# Regulators1.net
KiCad netlist of a schematic drawn in Altium Designer
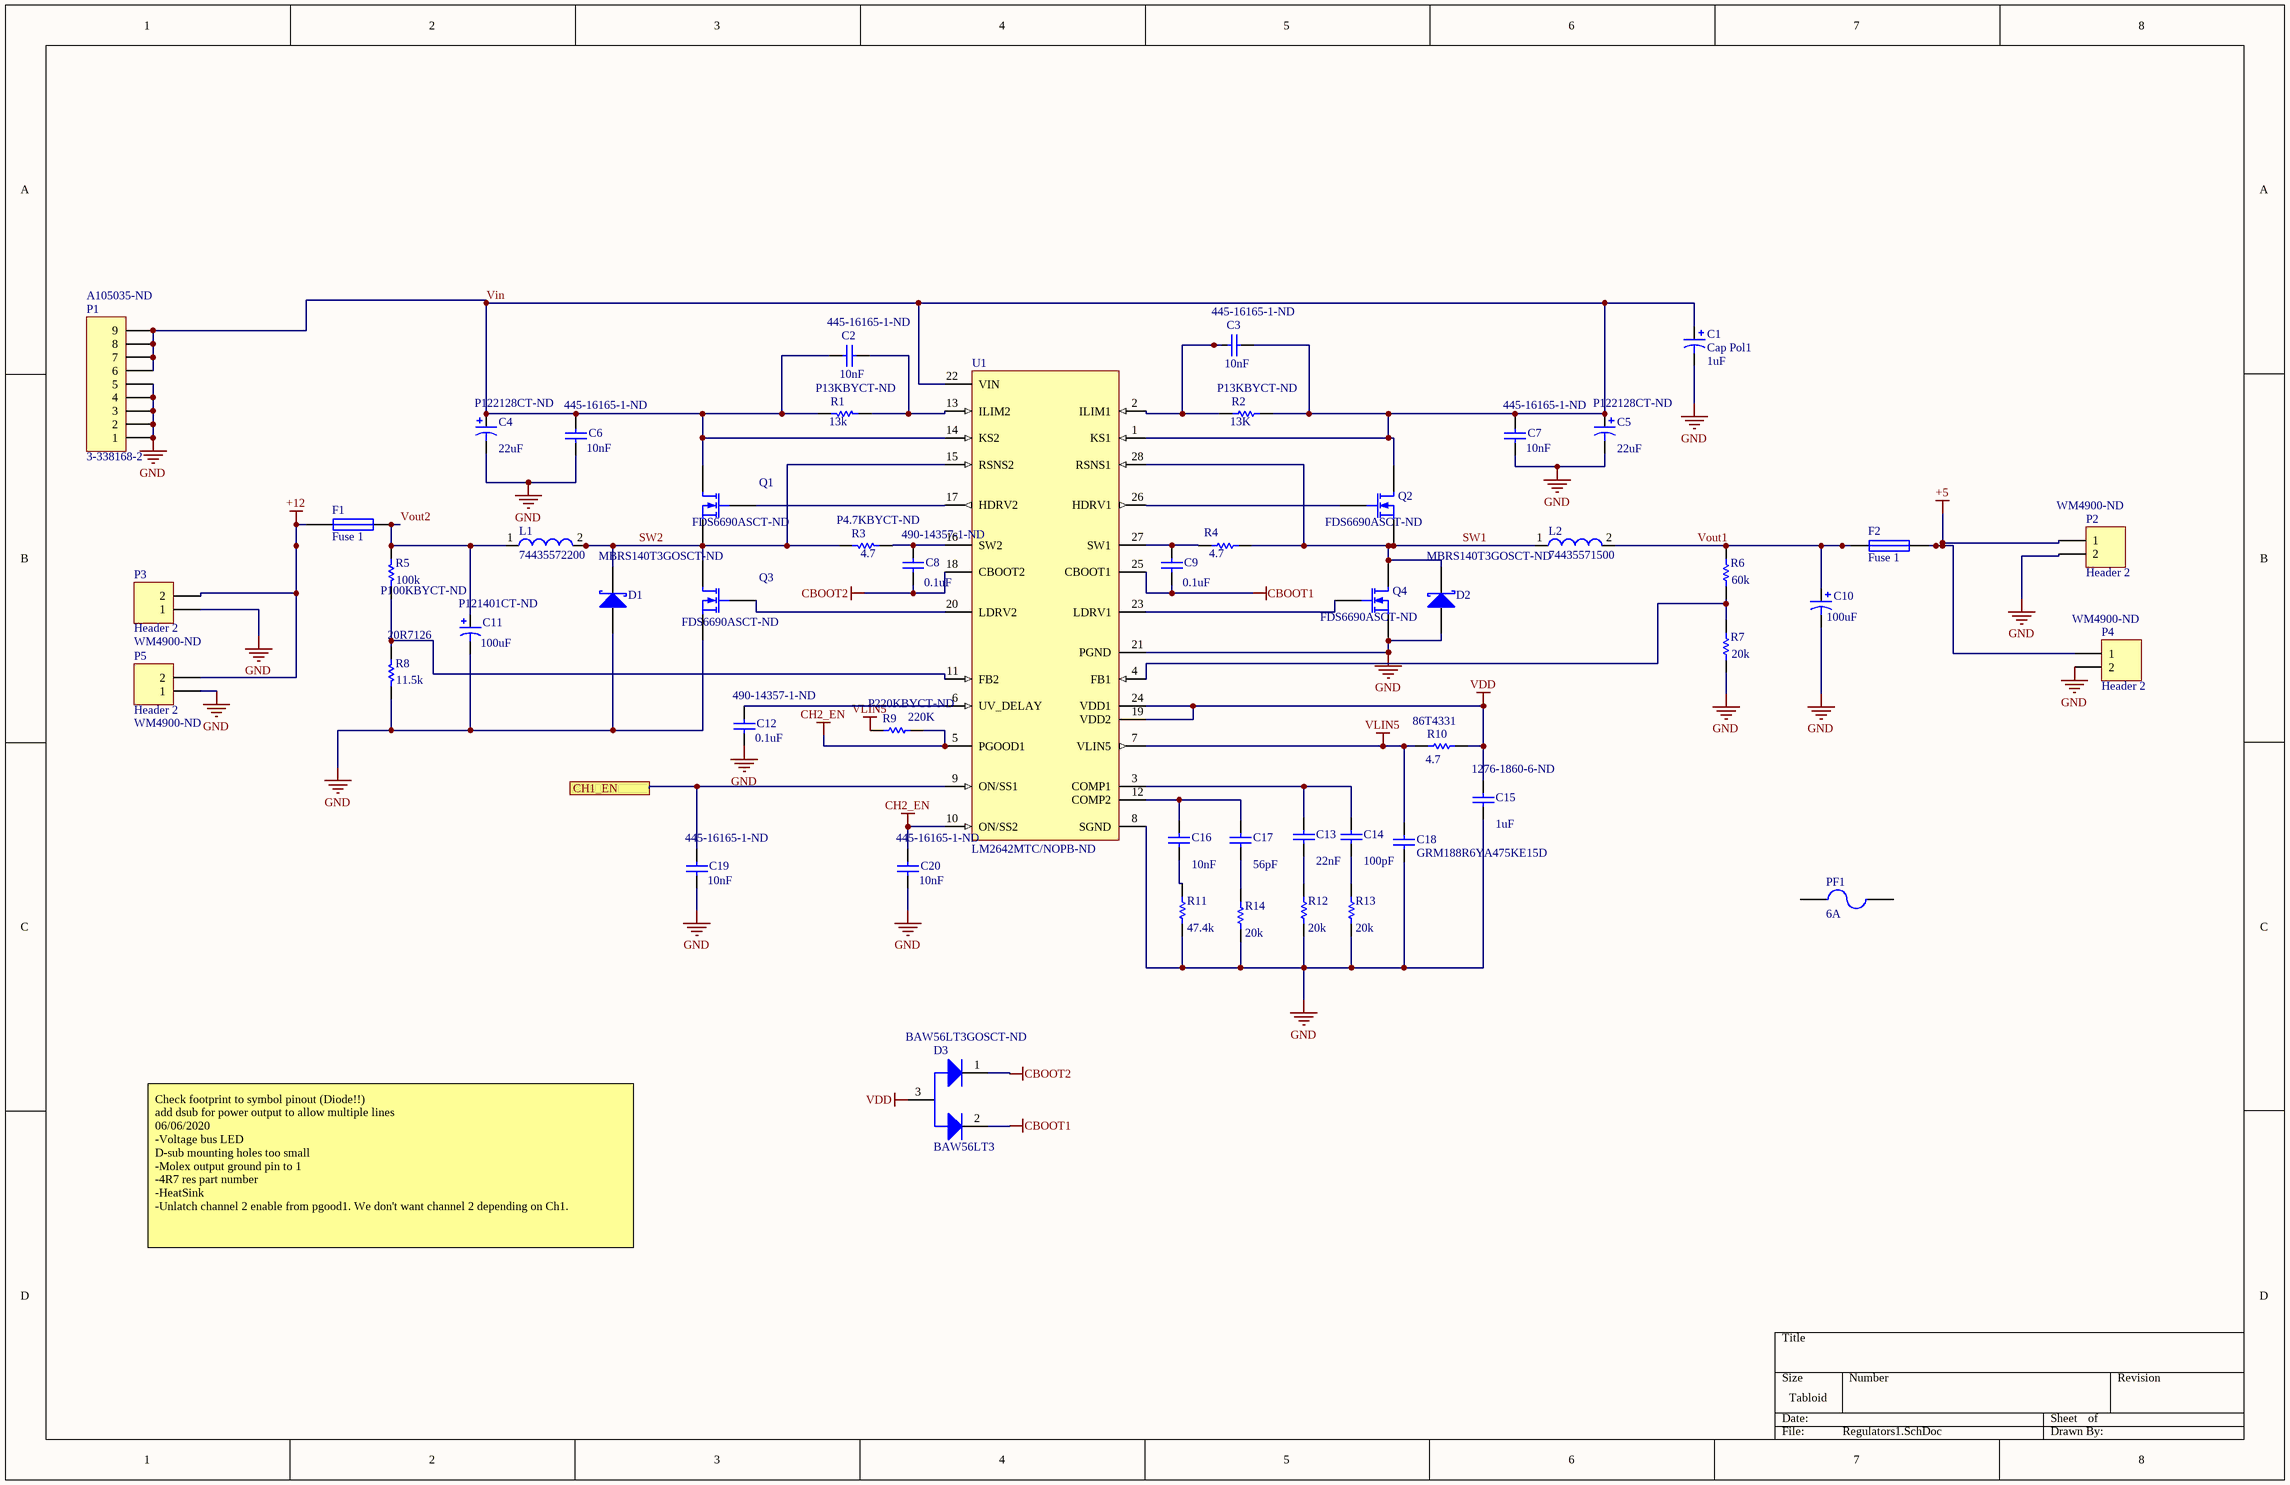
[diagram p0: Regulators1.SchDoc]

(export (version "E")
  (design (tool "Eeschema 10.0.6"))
  (components
    (comp (ref "C1")
      (value "Cap Pol1")
      (footprint "1u50VcapE")
      (description "Polarized Capacitor (Radial)")
      (fields (field (name "ALTIUM_VALUE") "1uF") (field (name "PUBLISHER") "Altium Limited"))
      (libsource (lib "") (part "Cap Pol1_1"))
    )
    (comp (ref "C2")
      (value "10nF")
      (footprint "1608[0603]")
      (description "CAP CER 10000PF 100V NP0 0603")
      (fields
        (field (name "SUPPLIER PART NUMBER 1") "445-16165-1-ND")
        (field (name "MANUFACTURER") "TDK")
        (field (name "MANUFACTURER PART NUMBER") "CGA3EANP02A103J080AC")
        (field (name "PUBLISHER") "Altium Limited")
      )
      (libsource (lib "Miscellaneous Devices") (part "Cap"))
    )
    (comp (ref "C3")
      (value "10nF")
      (footprint "1608[0603]")
      (description "CAP CER 10000PF 100V NP0 0603")
      (fields
        (field (name "SUPPLIER PART NUMBER 1") "445-16165-1-ND")
        (field (name "MANUFACTURER") "TDK")
        (field (name "MANUFACTURER PART NUMBER") "CGA3EANP02A103J080AC")
        (field (name "PUBLISHER") "Altium Limited")
      )
      (libsource (lib "Miscellaneous Devices") (part "Cap"))
    )
    (comp (ref "C4")
      (value "22uF")
      (footprint "CAPAE660X800N")
      (description "Polarized Capacitor (Radial)")
      (fields
        (field (name "SUPPLIER PART NUMBER 1") "P122128CT-ND")
        (field (name "Comment") "Cap Pol1")
        (field (name "PUBLISHER") "Altium Limited")
      )
      (libsource (lib "Miscellaneous Devices") (part "Cap Pol1"))
    )
    (comp (ref "C5")
      (value "22uF")
      (footprint "CAPAE660X800N")
      (description "Polarized Capacitor (Radial)")
      (fields
        (field (name "SUPPLIER PART NUMBER 1") "P122128CT-ND")
        (field (name "Comment") "Cap Pol1")
        (field (name "PUBLISHER") "Altium Limited")
      )
      (libsource (lib "") (part "Cap Pol1_1"))
    )
    (comp (ref "C6")
      (value "10nF")
      (footprint "1608[0603]")
      (description "CAP CER 10000PF 100V NP0 0603")
      (fields
        (field (name "SUPPLIER PART NUMBER 1") "445-16165-1-ND")
        (field (name "MANUFACTURER") "TDK")
        (field (name "MANUFACTURER PART NUMBER") "CGA3EANP02A103J080AC")
        (field (name "PUBLISHER") "Altium Limited")
      )
      (libsource (lib "Miscellaneous Devices") (part "Cap"))
    )
    (comp (ref "C7")
      (value "10nF")
      (footprint "1608[0603]")
      (description "CAP CER 10000PF 100V NP0 0603")
      (fields
        (field (name "SUPPLIER PART NUMBER 1") "445-16165-1-ND")
        (field (name "MANUFACTURER") "TDK")
        (field (name "MANUFACTURER PART NUMBER") "CGA3EANP02A103J080AC")
        (field (name "PUBLISHER") "Altium Limited")
      )
      (libsource (lib "Miscellaneous Devices") (part "Cap"))
    )
    (comp (ref "C8")
      (value "0.1uF")
      (footprint "1608[0603]")
      (description "CAP CER 0.1UF 50V X7R 0603")
      (fields
        (field (name "SUPPLIER PART NUMBER 1") "490-14357-1-ND")
        (field (name "MANUFACTURER") "Murata")
        (field (name "MANUFACTURER PART NUMBER") "GCM188R71H104JA57D")
        (field (name "PUBLISHER") "Altium Limited")
      )
      (libsource (lib "Miscellaneous Devices") (part "Cap"))
    )
    (comp (ref "C9")
      (value "0.1uF")
      (footprint "1608[0603]")
      (description "CAP CER 0.1UF 50V X7R 0603")
      (fields
        (field (name "MANUFACTURER") "Murata")
        (field (name "MANUFACTURER PART NUMBER") "GCM188R71H104JA57D")
        (field (name "PUBLISHER") "Altium Limited")
      )
      (libsource (lib "Miscellaneous Devices") (part "Cap"))
    )
    (comp (ref "C10")
      (value "100uF")
      (footprint "CAPAE660X800N")
      (description "Polarized Capacitor (Radial)")
      (fields (field (name "Comment") "Cap Pol1") (field (name "PUBLISHER") "Altium Limited"))
      (libsource (lib "") (part "Cap Pol1_1"))
    )
    (comp (ref "C11")
      (value "100uF")
      (footprint "CAPAE660X800N")
      (description "Polarized Capacitor (Radial)")
      (fields
        (field (name "SUPPLIER PART NUMBER 1") "P121401CT-ND")
        (field (name "Comment") "Cap Pol1")
        (field (name "PUBLISHER") "Altium Limited")
      )
      (libsource (lib "Miscellaneous Devices") (part "Cap Pol1"))
    )
    (comp (ref "C12")
      (value "0.1uF")
      (footprint "1608[0603]")
      (description "CAP CER 0.1UF 50V X7R 0603")
      (fields
        (field (name "SUPPLIER PART NUMBER 1") "490-14357-1-ND")
        (field (name "MANUFACTURER") "Murata")
        (field (name "MANUFACTURER PART NUMBER") "GCM188R71H104JA57D")
        (field (name "PUBLISHER") "Altium Limited")
      )
      (libsource (lib "Miscellaneous Devices") (part "Cap"))
    )
    (comp (ref "C13")
      (value "22nF")
      (footprint "1608[0603]")
      (description "0603 22 nF 50 V ±5% Tolerance X7R SMT Multilayer Ceramic Capacitor")
      (fields
        (field (name "MANUFACTURER") "Walsin Technologies")
        (field (name "MANUFACTURER PART NUMBER") "0603B223J500CT")
        (field (name "PUBLISHER") "Altium Limited")
      )
      (libsource (lib "Miscellaneous Devices") (part "Cap"))
    )
    (comp (ref "C14")
      (value "100pF")
      (footprint "1608[0603]")
      (description "Multilayer Ceramic Capacitors MLCC - SMD/SMT 100pF 50V X7R 5%")
      (fields
        (field (name "MANUFACTURER") "Yageo")
        (field (name "MANUFACTURER PART NUMBER") "CC0603JRX7R9BB101")
        (field (name "PUBLISHER") "Altium Limited")
      )
      (libsource (lib "Miscellaneous Devices") (part "Cap"))
    )
    (comp (ref "C15")
      (value "1uF")
      (footprint "1608[0603]")
      (description "Cap Ceramic 1uF 50V X5R 10% SMD 0603 85C Cardboard T/R")
      (fields
        (field (name "SUPPLIER PART NUMBER 1") "1276-1860-6-ND")
        (field (name "MANUFACTURER") "Samsung")
        (field (name "MANUFACTURER PART NUMBER") "CL10A105KB8NNNC")
        (field (name "PUBLISHER") "Altium Limited")
      )
      (libsource (lib "Miscellaneous Devices") (part "Cap"))
    )
    (comp (ref "C16")
      (value "10nF")
      (footprint "1608[0603]")
      (description "CAP CER 10000PF 100V NP0 0603")
      (fields
        (field (name "MANUFACTURER") "TDK")
        (field (name "MANUFACTURER PART NUMBER") "CGA3EANP02A103J080AC")
        (field (name "PUBLISHER") "Altium Limited")
      )
      (libsource (lib "Miscellaneous Devices") (part "Cap"))
    )
    (comp (ref "C17")
      (value "56pF")
      (footprint "1608[0603]")
      (description "Chip Capacitor 0603 MLCC NPO 56 pF+/- 1% 50 V T&R GP")
      (fields
        (field (name "MANUFACTURER") "Walsin Technologies")
        (field (name "MANUFACTURER PART NUMBER") "0603N560F500CT")
        (field (name "PUBLISHER") "Altium Limited")
      )
      (libsource (lib "Miscellaneous Devices") (part "Cap"))
    )
    (comp (ref "C18")
      (value "GRM188R6YA475KE15D")
      (footprint "CAPC1608X90X35LL10T15")
      (fields (field (name "MANUFACTURER") "Murata"))
      (libsource (lib "Altium Content Vault") (part "CAP"))
    )
    (comp (ref "C19")
      (value "10nF")
      (footprint "1608[0603]")
      (description "CAP CER 10000PF 100V NP0 0603")
      (fields
        (field (name "SUPPLIER PART NUMBER 1") "445-16165-1-ND")
        (field (name "MANUFACTURER") "TDK")
        (field (name "MANUFACTURER PART NUMBER") "CGA3EANP02A103J080AC")
        (field (name "PUBLISHER") "Altium Limited")
      )
      (libsource (lib "Miscellaneous Devices") (part "Cap"))
    )
    (comp (ref "C20")
      (value "10nF")
      (footprint "1608[0603]")
      (description "CAP CER 10000PF 100V NP0 0603")
      (fields
        (field (name "SUPPLIER PART NUMBER 1") "445-16165-1-ND")
        (field (name "MANUFACTURER") "TDK")
        (field (name "MANUFACTURER PART NUMBER") "CGA3EANP02A103J080AC")
        (field (name "PUBLISHER") "Altium Limited")
      )
      (libsource (lib "Miscellaneous Devices") (part "Cap"))
    )
    (comp (ref "D1")
      (value "Diode MBRS140t3")
      (footprint "*DIOM5227X270N_S1M(Primary)")
      (description "Schottky Rectifier")
      (fields
        (field (name "SUPPLIER PART NUMBER 1") "MBRS140T3GOSCT-ND")
        (field (name "PUBLISHER") "Altium Limited")
      )
      (libsource (lib "Miscellaneous Devices") (part "Diode 18TQ045"))
    )
    (comp (ref "D2")
      (value "Diode MBRS140t3")
      (footprint "*DIOM5227X270N_S1M(Primary)")
      (description "Schottky Rectifier")
      (fields
        (field (name "SUPPLIER PART NUMBER 1") "MBRS140T3GOSCT-ND")
        (field (name "PUBLISHER") "Altium Limited")
      )
      (libsource (lib "Miscellaneous Devices") (part "Diode 18TQ045"))
    )
    (comp (ref "D3")
      (value "BAW56LT3")
      (footprint "ONSC-SOT-23-3-318-08_V")
      (description "Diode Small Signal Switching 70V 0.2A Automotive 3-Pin SOT-23 T/R")
      (fields
        (field (name "MANUFACTURER") "On Semiconductor")
        (field (name "SUPPLIER PART NUMBER 1") "BAW56LT3GOSCT-ND")
        (field (name "MANUFACTURER PART NUMBER") "BAW56LT3G")
      )
      (libsource (lib "ON Semi Small Signal Switching Diodes") (part "BAW56LT3"))
    )
    (comp (ref "F1")
      (value "Fuse 1")
      (footprint "C1206")
      (description "Fuse")
      (fields (field (name "PUBLISHER") "Altium Limited"))
      (libsource (lib "Miscellaneous Devices") (part "Fuse 1"))
    )
    (comp (ref "F2")
      (value "Fuse 1")
      (footprint "C1206")
      (description "Fuse")
      (fields (field (name "PUBLISHER") "Altium Limited"))
      (libsource (lib "Miscellaneous Devices") (part "Fuse 1"))
    )
    (comp (ref "L1")
      (value "74435572200")
      (footprint "WE-HCI-1890")
      (description "SMD Flat Wire High Current Inductor WE-HCI, L=22.0 µH")
      (libsource (lib "Altium Content Vault") (part "PAS-IND-INDUCTOR-2"))
    )
    (comp (ref "L2")
      (value "74435571500")
      (footprint "WE-HCI-1890")
      (description "SMD Flat Wire High Current Inductor WE-HCI, L=15.0 µH")
      (libsource (lib "Altium Content Vault") (part "PAS-IND-INDUCTOR-2"))
    )
    (comp (ref "P1")
      (value "3-338168-2")
      (footprint "CONN_3-338168-2")
      (description "Header, 9-Pin")
      (fields
        (field (name "SUPPLIER PART NUMBER 1") "A105035-ND")
        (field (name "PUBLISHER") "Altium Limited")
      )
      (libsource (lib "Miscellaneous Connectors") (part "Header 9"))
    )
    (comp (ref "P2")
      (value "Header 2")
      (footprint "WM4900-ND")
      (description "Header, 2-Pin")
      (fields (field (name "SUPPLIER PART NUMBER 1") "WM4900-ND") (field (name "PUBLISHER") "Altium Limited"))
      (libsource (lib "") (part "Header 2_1"))
    )
    (comp (ref "P3")
      (value "Header 2")
      (footprint "WM4900-ND")
      (description "Header, 2-Pin")
      (fields (field (name "SUPPLIER PART NUMBER 1") "WM4900-ND") (field (name "PUBLISHER") "Altium Limited"))
      (libsource (lib "Miscellaneous Connectors") (part "Header 2"))
    )
    (comp (ref "P4")
      (value "Header 2")
      (footprint "WM4900-ND")
      (description "Header, 2-Pin")
      (fields (field (name "SUPPLIER PART NUMBER 1") "WM4900-ND") (field (name "PUBLISHER") "Altium Limited"))
      (libsource (lib "") (part "Header 2_1"))
    )
    (comp (ref "P5")
      (value "Header 2")
      (footprint "WM4900-ND")
      (description "Header, 2-Pin")
      (fields (field (name "SUPPLIER PART NUMBER 1") "WM4900-ND") (field (name "PUBLISHER") "Altium Limited"))
      (libsource (lib "Miscellaneous Connectors") (part "Header 2"))
    )
    (comp (ref "PF1")
      (value "6A")
      (footprint "RESC3216X125N")
      (description "Fuse")
      (fields (field (name "PUBLISHER") "Altium Limited"))
      (libsource (lib "Miscellaneous Devices") (part "Fuse 2"))
    )
    (comp (ref "Q1")
      (value "MOSFET-N")
      (footprint "SOIC127P600X175-8N:*SOIC127P600X175-8N")
      (description "N-Channel MOSFET")
      (fields
        (field (name "SUPPLIER PART NUMBER 1") "FDS6690ASCT-ND")
        (field (name "PUBLISHER") "Altium Limited")
      )
      (libsource (lib "Miscellaneous Devices") (part "MOSFET-N"))
    )
    (comp (ref "Q2")
      (value "MOSFET-N")
      (footprint "SOIC127P600X175-8N:*SOIC127P600X175-8N")
      (description "N-Channel MOSFET")
      (fields
        (field (name "SUPPLIER PART NUMBER 1") "FDS6690ASCT-ND")
        (field (name "PUBLISHER") "Altium Limited")
      )
      (libsource (lib "Miscellaneous Devices") (part "MOSFET-N"))
    )
    (comp (ref "Q3")
      (value "MOSFET-N")
      (footprint "SOIC127P600X175-8N:*SOIC127P600X175-8N")
      (description "N-Channel MOSFET")
      (fields
        (field (name "SUPPLIER PART NUMBER 1") "FDS6690ASCT-ND")
        (field (name "PUBLISHER") "Altium Limited")
      )
      (libsource (lib "Miscellaneous Devices") (part "MOSFET-N"))
    )
    (comp (ref "Q4")
      (value "MOSFET-N")
      (footprint "SOIC127P600X175-8N:*SOIC127P600X175-8N")
      (description "N-Channel MOSFET")
      (fields
        (field (name "SUPPLIER PART NUMBER 1") "FDS6690ASCT-ND")
        (field (name "PUBLISHER") "Altium Limited")
      )
      (libsource (lib "Miscellaneous Devices") (part "MOSFET-N"))
    )
    (comp (ref "R1")
      (value "13k")
      (footprint "1608[0603]")
      (description "PANASONIC   ERJPA3F1302V   RESISTOR, ERJP, 13 KOHM, 0603, 0.25W, 1%")
      (fields
        (field (name "SUPPLIER PART NUMBER 1") "P13KBYCT-ND")
        (field (name "MANUFACTURER") "Panasonic")
        (field (name "MANUFACTURER PART NUMBER") "ERJ-PA3F1302V")
        (field (name "PUBLISHER") "Altium Limited")
      )
      (libsource (lib "Miscellaneous Devices") (part "Res1"))
    )
    (comp (ref "R2")
      (value "13K")
      (footprint "1608[0603]")
      (description "PANASONIC   ERJPA3F1302V   RESISTOR, ERJP, 13 KOHM, 0603, 0.25W, 1%")
      (fields
        (field (name "SUPPLIER PART NUMBER 1") "P13KBYCT-ND")
        (field (name "MANUFACTURER") "Panasonic")
        (field (name "MANUFACTURER PART NUMBER") "ERJ-PA3F1302V")
        (field (name "PUBLISHER") "Altium Limited")
      )
      (libsource (lib "Miscellaneous Devices") (part "Res1"))
    )
    (comp (ref "R3")
      (value "4.7")
      (footprint "1608[0603]")
      (description "PANASONIC   ERJPA3F4701V   RESISTOR, ERJP, 4.7KOHM, 0603, 0.25W, 1%")
      (fields
        (field (name "SUPPLIER PART NUMBER 1") "P4.7KBYCT-ND")
        (field (name "MANUFACTURER") "Panasonic")
        (field (name "MANUFACTURER PART NUMBER") "ERJ-PA3F4701V")
        (field (name "PUBLISHER") "Altium Limited")
      )
      (libsource (lib "Miscellaneous Devices") (part "Res1"))
    )
    (comp (ref "R4")
      (value "4.7")
      (footprint "1608[0603]")
      (description "PANASONIC   ERJPA3F4701V   RESISTOR, ERJP, 4.7KOHM, 0603, 0.25W, 1%")
      (fields
        (field (name "MANUFACTURER") "Panasonic")
        (field (name "MANUFACTURER PART NUMBER") "ERJ-PA3F4701V")
        (field (name "PUBLISHER") "Altium Limited")
      )
      (libsource (lib "Miscellaneous Devices") (part "Res1"))
    )
    (comp (ref "R5")
      (value "100k")
      (footprint "1608[0603]")
      (description "ERJPA3 Resistors 0.25W 0603 100K 1%")
      (fields
        (field (name "SUPPLIER PART NUMBER 1") "P100KBYCT-ND")
        (field (name "MANUFACTURER") "Panasonic")
        (field (name "MANUFACTURER PART NUMBER") "ERJ-PA3F1003V")
        (field (name "PUBLISHER") "Altium Limited")
      )
      (libsource (lib "Miscellaneous Devices") (part "Res1"))
    )
    (comp (ref "R6")
      (value "60k")
      (footprint "1608[0603]")
      (description "RES SMD 60.4K OHM 0.1% 1/5W 0603")
      (fields
        (field (name "MANUFACTURER") "Panasonic")
        (field (name "MANUFACTURER PART NUMBER") "ERJ-PB3B6042V")
        (field (name "PUBLISHER") "Altium Limited")
      )
      (libsource (lib "Miscellaneous Devices") (part "Res1"))
    )
    (comp (ref "R7")
      (value "20k")
      (footprint "1608[0603]")
      (description "RES SMD 20K OHM 0.1% 1/10W 0603")
      (fields
        (field (name "MANUFACTURER") "TE Connectivity AMP")
        (field (name "MANUFACTURER PART NUMBER") "RP73D1J20KBTG")
        (field (name "PUBLISHER") "Altium Limited")
      )
      (libsource (lib "Miscellaneous Devices") (part "Res1"))
    )
    (comp (ref "R8")
      (value "11.5k")
      (footprint "1608[0603]")
      (description "Thin Film Resistors RN 0603 11K5 0.1% 10PPM CUT LENGTH")
      (fields
        (field (name "SUPPLIER PART NUMBER 1") "20R7126")
        (field (name "MANUFACTURER") "TE Connectivity")
        (field (name "MANUFACTURER PART NUMBER") "RN73C1J11K5BTG")
        (field (name "PUBLISHER") "Altium Limited")
      )
      (libsource (lib "Miscellaneous Devices") (part "Res1"))
    )
    (comp (ref "R9")
      (value "220K")
      (footprint "1608[0603]")
      (description "RES SMD 220K OHM 1% 1/4W 0603")
      (fields
        (field (name "SUPPLIER PART NUMBER 1") "P220KBYCT-ND")
        (field (name "MANUFACTURER") "Panasonic")
        (field (name "MANUFACTURER PART NUMBER") "ERJ-PA3F2203V")
        (field (name "PUBLISHER") "Altium Limited")
      )
      (libsource (lib "Miscellaneous Devices") (part "Res1"))
    )
    (comp (ref "R10")
      (value "4.7")
      (footprint "1608[0603]")
      (description "MULTICOMP - MCSR06X4701FTL - RES, CERAMIC, 4K7, 1%, 0.1W, 0603")
      (fields
        (field (name "SUPPLIER PART NUMBER 1") "86T4331")
        (field (name "MANUFACTURER") "Multicomp")
        (field (name "MANUFACTURER PART NUMBER") "MCSR06X4701FTL")
        (field (name "PUBLISHER") "Altium Limited")
      )
      (libsource (lib "Miscellaneous Devices") (part "Res1"))
    )
    (comp (ref "R11")
      (value "47.4k")
      (footprint "1608[0603]")
      (description "RES SMD 47.5K OHM 0.1% 1/5W 0603")
      (fields
        (field (name "MANUFACTURER") "Panasonic")
        (field (name "MANUFACTURER PART NUMBER") "ERJ-PB3B4752V")
        (field (name "PUBLISHER") "Altium Limited")
      )
      (libsource (lib "Miscellaneous Devices") (part "Res1"))
    )
    (comp (ref "R12")
      (value "20k")
      (footprint "1608[0603]")
      (description "RES SMD 20K OHM 0.1% 1/10W 0603")
      (fields
        (field (name "MANUFACTURER") "TE Connectivity AMP")
        (field (name "MANUFACTURER PART NUMBER") "RP73D1J20KBTG")
        (field (name "PUBLISHER") "Altium Limited")
      )
      (libsource (lib "Miscellaneous Devices") (part "Res1"))
    )
    (comp (ref "R13")
      (value "20k")
      (footprint "1608[0603]")
      (description "RES SMD 20K OHM 0.1% 1/10W 0603")
      (fields
        (field (name "MANUFACTURER") "TE Connectivity AMP")
        (field (name "MANUFACTURER PART NUMBER") "RP73D1J20KBTG")
        (field (name "PUBLISHER") "Altium Limited")
      )
      (libsource (lib "Miscellaneous Devices") (part "Res1"))
    )
    (comp (ref "R14")
      (value "20k")
      (footprint "1608[0603]")
      (description "RES SMD 20K OHM 0.1% 1/10W 0603")
      (fields
        (field (name "MANUFACTURER") "TE Connectivity AMP")
        (field (name "MANUFACTURER PART NUMBER") "RP73D1J20KBTG")
        (field (name "PUBLISHER") "Altium Limited")
      )
      (libsource (lib "Miscellaneous Devices") (part "Res1"))
    )
    (comp (ref "U1")
      (value "LM2642MTC/NOPB")
      (footprint "MTC28_N")
      (description "Two-Phase Synchronous Step-Down Switching Controller, 28-pin TSSOP, Pb-Free")
      (fields
        (field (name "MANUFACTURER") "National Semiconductor")
        (field (name "SUPPLIER PART NUMBER 1") "LM2642MTC/NOPB-ND")
      )
      (libsource (lib "National Semiconductor Switcher") (part "LM2642MTC/NOPB"))
    )
  )
  (nets
    (net (code "1") (name "+5") (class "Default")
      (node (ref "F2") (pin "2") (pinfunction "2_2") (pintype "passive"))
      (node (ref "P2") (pin "1") (pinfunction "1_1") (pintype "passive"))
      (node (ref "P4") (pin "1") (pinfunction "1_1") (pintype "passive"))
    )
    (net (code "2") (name "+12") (class "Default")
      (node (ref "F1") (pin "1") (pinfunction "1_1") (pintype "passive"))
      (node (ref "P3") (pin "2") (pinfunction "2_2") (pintype "passive"))
      (node (ref "P5") (pin "2") (pinfunction "2_2") (pintype "passive"))
    )
    (net (code "3") (name "/CH1_EN") (class "Default")
      (node (ref "C19") (pin "2") (pinfunction "2_2") (pintype "passive"))
      (node (ref "U1") (pin "9") (pinfunction "ON/SS1_9") (pintype "input"))
    )
    (net (code "4") (name "/SW1") (class "Default")
      (node (ref "D2") (pin "1") (pinfunction "K_1") (pintype "passive"))
      (node (ref "L2") (pin "1") (pinfunction "1_1") (pintype "passive"))
      (node (ref "Q2") (pin "3") (pinfunction "S_3") (pintype "passive"))
      (node (ref "Q4") (pin "1") (pinfunction "D_1") (pintype "passive"))
      (node (ref "R4") (pin "2") (pinfunction "2_2") (pintype "passive"))
      (node (ref "U1") (pin "28") (pinfunction "RSNS1_28") (pintype "input"))
    )
    (net (code "5") (name "/SW2") (class "Default")
      (node (ref "D1") (pin "1") (pinfunction "K_1") (pintype "passive"))
      (node (ref "L1") (pin "2") (pinfunction "2_2") (pintype "passive"))
      (node (ref "Q1") (pin "3") (pinfunction "S_3") (pintype "passive"))
      (node (ref "Q3") (pin "1") (pinfunction "D_1") (pintype "passive"))
      (node (ref "R3") (pin "2") (pinfunction "2_2") (pintype "passive"))
      (node (ref "U1") (pin "15") (pinfunction "RSNS2_15") (pintype "input"))
    )
    (net (code "6") (name "/Vin") (class "Default")
      (node (ref "C1") (pin "1") (pinfunction "1_1") (pintype "passive"))
      (node (ref "C2") (pin "2") (pinfunction "2_2") (pintype "passive"))
      (node (ref "C3") (pin "1") (pinfunction "1_1") (pintype "passive"))
      (node (ref "C4") (pin "1") (pinfunction "1_1") (pintype "passive"))
      (node (ref "C5") (pin "1") (pinfunction "1_1") (pintype "passive"))
      (node (ref "C6") (pin "2") (pinfunction "2_2") (pintype "passive"))
      (node (ref "C7") (pin "2") (pinfunction "2_2") (pintype "passive"))
      (node (ref "P1") (pin "6") (pinfunction "6_6") (pintype "passive"))
      (node (ref "P1") (pin "7") (pinfunction "7_7") (pintype "passive"))
      (node (ref "P1") (pin "8") (pinfunction "8_8") (pintype "passive"))
      (node (ref "P1") (pin "9") (pinfunction "9_9") (pintype "passive"))
      (node (ref "Q1") (pin "1") (pinfunction "D_1") (pintype "passive"))
      (node (ref "Q2") (pin "1") (pinfunction "D_1") (pintype "passive"))
      (node (ref "R1") (pin "2") (pinfunction "2_2") (pintype "passive"))
      (node (ref "R2") (pin "2") (pinfunction "2_2") (pintype "passive"))
      (node (ref "U1") (pin "1") (pinfunction "KS1_1") (pintype "input"))
      (node (ref "U1") (pin "14") (pinfunction "KS2_14") (pintype "input"))
      (node (ref "U1") (pin "22") (pinfunction "VIN_22") (pintype "power_in"))
    )
    (net (code "7") (name "/Vout1") (class "Default")
      (node (ref "C10") (pin "1") (pinfunction "1_1") (pintype "passive"))
      (node (ref "F2") (pin "1") (pinfunction "1_1") (pintype "passive"))
      (node (ref "L2") (pin "2") (pinfunction "2_2") (pintype "passive"))
      (node (ref "R6") (pin "2") (pinfunction "2_2") (pintype "passive"))
    )
    (net (code "8") (name "/Vout2") (class "Default")
      (node (ref "C11") (pin "1") (pinfunction "1_1") (pintype "passive"))
      (node (ref "F1") (pin "2") (pinfunction "2_2") (pintype "passive"))
      (node (ref "L1") (pin "1") (pinfunction "1_1") (pintype "passive"))
      (node (ref "R5") (pin "2") (pinfunction "2_2") (pintype "passive"))
    )
    (net (code "9") (name "CBOOT1") (class "Default")
      (node (ref "C9") (pin "1") (pinfunction "1_1") (pintype "passive"))
      (node (ref "D3") (pin "2") (pinfunction "K2_2") (pintype "passive"))
      (node (ref "U1") (pin "25") (pinfunction "CBOOT1_25") (pintype "passive"))
    )
    (net (code "10") (name "CBOOT2") (class "Default")
      (node (ref "C8") (pin "1") (pinfunction "1_1") (pintype "passive"))
      (node (ref "D3") (pin "1") (pinfunction "K1_1") (pintype "passive"))
      (node (ref "U1") (pin "18") (pinfunction "CBOOT2_18") (pintype "passive"))
    )
    (net (code "11") (name "CH2_EN") (class "Default")
      (node (ref "C20") (pin "2") (pinfunction "2_2") (pintype "passive"))
      (node (ref "R9") (pin "2") (pinfunction "2_2") (pintype "passive"))
      (node (ref "U1") (pin "10") (pinfunction "ON/SS2_10") (pintype "input"))
      (node (ref "U1") (pin "5") (pinfunction "PGOOD1_5") (pintype "open_collector"))
    )
    (net (code "12") (name "GND") (class "Default")
      (node (ref "C1") (pin "2") (pinfunction "2_2") (pintype "passive"))
      (node (ref "C10") (pin "2") (pinfunction "2_2") (pintype "passive"))
      (node (ref "C11") (pin "2") (pinfunction "2_2") (pintype "passive"))
      (node (ref "C12") (pin "1") (pinfunction "1_1") (pintype "passive"))
      (node (ref "C15") (pin "1") (pinfunction "1_1") (pintype "passive"))
      (node (ref "C18") (pin "1") (pinfunction "1_1") (pintype "passive"))
      (node (ref "C19") (pin "1") (pinfunction "1_1") (pintype "passive"))
      (node (ref "C20") (pin "1") (pinfunction "1_1") (pintype "passive"))
      (node (ref "C4") (pin "2") (pinfunction "2_2") (pintype "passive"))
      (node (ref "C5") (pin "2") (pinfunction "2_2") (pintype "passive"))
      (node (ref "C6") (pin "1") (pinfunction "1_1") (pintype "passive"))
      (node (ref "C7") (pin "1") (pinfunction "1_1") (pintype "passive"))
      (node (ref "D1") (pin "3") (pinfunction "A_3") (pintype "passive"))
      (node (ref "D2") (pin "3") (pinfunction "A_3") (pintype "passive"))
      (node (ref "P1") (pin "1") (pinfunction "1_1") (pintype "passive"))
      (node (ref "P1") (pin "2") (pinfunction "2_2") (pintype "passive"))
      (node (ref "P1") (pin "3") (pinfunction "3_3") (pintype "passive"))
      (node (ref "P1") (pin "4") (pinfunction "4_4") (pintype "passive"))
      (node (ref "P1") (pin "5") (pinfunction "5_5") (pintype "passive"))
      (node (ref "P2") (pin "2") (pinfunction "2_2") (pintype "passive"))
      (node (ref "P3") (pin "1") (pinfunction "1_1") (pintype "passive"))
      (node (ref "P4") (pin "2") (pinfunction "2_2") (pintype "passive"))
      (node (ref "P5") (pin "1") (pinfunction "1_1") (pintype "passive"))
      (node (ref "Q3") (pin "3") (pinfunction "S_3") (pintype "passive"))
      (node (ref "Q4") (pin "3") (pinfunction "S_3") (pintype "passive"))
      (node (ref "R11") (pin "1") (pinfunction "1_1") (pintype "passive"))
      (node (ref "R12") (pin "1") (pinfunction "1_1") (pintype "passive"))
      (node (ref "R13") (pin "1") (pinfunction "1_1") (pintype "passive"))
      (node (ref "R14") (pin "1") (pinfunction "1_1") (pintype "passive"))
      (node (ref "R7") (pin "1") (pinfunction "1_1") (pintype "passive"))
      (node (ref "R8") (pin "1") (pinfunction "1_1") (pintype "passive"))
      (node (ref "U1") (pin "21") (pinfunction "PGND_21") (pintype "power_in"))
      (node (ref "U1") (pin "8") (pinfunction "SGND_8") (pintype "power_in"))
    )
    (net (code "13") (name "Net-(C13-Pad1)") (class "Default")
      (node (ref "C13") (pin "1") (pinfunction "1_1") (pintype "passive"))
      (node (ref "R12") (pin "2") (pinfunction "2_2") (pintype "passive"))
    )
    (net (code "14") (name "Net-(C14-Pad1)") (class "Default")
      (node (ref "C14") (pin "1") (pinfunction "1_1") (pintype "passive"))
      (node (ref "R13") (pin "2") (pinfunction "2_2") (pintype "passive"))
    )
    (net (code "15") (name "Net-(C16-Pad1)") (class "Default")
      (node (ref "C16") (pin "1") (pinfunction "1_1") (pintype "passive"))
      (node (ref "R11") (pin "2") (pinfunction "2_2") (pintype "passive"))
    )
    (net (code "16") (name "Net-(C17-Pad1)") (class "Default")
      (node (ref "C17") (pin "1") (pinfunction "1_1") (pintype "passive"))
      (node (ref "R14") (pin "2") (pinfunction "2_2") (pintype "passive"))
    )
    (net (code "17") (name "Net-(Q1-G)") (class "Default")
      (node (ref "Q1") (pin "2") (pinfunction "G_2") (pintype "passive"))
      (node (ref "U1") (pin "17") (pinfunction "HDRV2_17") (pintype "output"))
    )
    (net (code "18") (name "Net-(Q2-G)") (class "Default")
      (node (ref "Q2") (pin "2") (pinfunction "G_2") (pintype "passive"))
      (node (ref "U1") (pin "26") (pinfunction "HDRV1_26") (pintype "output"))
    )
    (net (code "19") (name "Net-(Q3-G)") (class "Default")
      (node (ref "Q3") (pin "2") (pinfunction "G_2") (pintype "passive"))
      (node (ref "U1") (pin "20") (pinfunction "LDRV2_20") (pintype "power_in"))
    )
    (net (code "20") (name "Net-(Q4-G)") (class "Default")
      (node (ref "Q4") (pin "2") (pinfunction "G_2") (pintype "passive"))
      (node (ref "U1") (pin "23") (pinfunction "LDRV1_23") (pintype "power_in"))
    )
    (net (code "21") (name "Net-(U1-COMP1)") (class "Default")
      (node (ref "C13") (pin "2") (pinfunction "2_2") (pintype "passive"))
      (node (ref "C14") (pin "2") (pinfunction "2_2") (pintype "passive"))
      (node (ref "U1") (pin "3") (pinfunction "COMP1_3") (pintype "passive"))
    )
    (net (code "22") (name "Net-(U1-COMP2)") (class "Default")
      (node (ref "C16") (pin "2") (pinfunction "2_2") (pintype "passive"))
      (node (ref "C17") (pin "2") (pinfunction "2_2") (pintype "passive"))
      (node (ref "U1") (pin "12") (pinfunction "COMP2_12") (pintype "passive"))
    )
    (net (code "23") (name "Net-(U1-FB1)") (class "Default")
      (node (ref "R6") (pin "1") (pinfunction "1_1") (pintype "passive"))
      (node (ref "R7") (pin "2") (pinfunction "2_2") (pintype "passive"))
      (node (ref "U1") (pin "4") (pinfunction "FB1_4") (pintype "input"))
    )
    (net (code "24") (name "Net-(U1-FB2)") (class "Default")
      (node (ref "R5") (pin "1") (pinfunction "1_1") (pintype "passive"))
      (node (ref "R8") (pin "2") (pinfunction "2_2") (pintype "passive"))
      (node (ref "U1") (pin "11") (pinfunction "FB2_11") (pintype "input"))
    )
    (net (code "25") (name "Net-(U1-ILIM1)") (class "Default")
      (node (ref "C3") (pin "2") (pinfunction "2_2") (pintype "passive"))
      (node (ref "R2") (pin "1") (pinfunction "1_1") (pintype "passive"))
      (node (ref "U1") (pin "2") (pinfunction "ILIM1_2") (pintype "input"))
    )
    (net (code "26") (name "Net-(U1-ILIM2)") (class "Default")
      (node (ref "C2") (pin "1") (pinfunction "1_1") (pintype "passive"))
      (node (ref "R1") (pin "1") (pinfunction "1_1") (pintype "passive"))
      (node (ref "U1") (pin "13") (pinfunction "ILIM2_13") (pintype "input"))
    )
    (net (code "27") (name "Net-(U1-SW1)") (class "Default")
      (node (ref "C9") (pin "2") (pinfunction "2_2") (pintype "passive"))
      (node (ref "R4") (pin "1") (pinfunction "1_1") (pintype "passive"))
      (node (ref "U1") (pin "27") (pinfunction "SW1_27") (pintype "power_in"))
    )
    (net (code "28") (name "Net-(U1-SW2)") (class "Default")
      (node (ref "C8") (pin "2") (pinfunction "2_2") (pintype "passive"))
      (node (ref "R3") (pin "1") (pinfunction "1_1") (pintype "passive"))
      (node (ref "U1") (pin "16") (pinfunction "SW2_16") (pintype "power_in"))
    )
    (net (code "29") (name "Net-(U1-UV_DELAY)") (class "Default")
      (node (ref "C12") (pin "2") (pinfunction "2_2") (pintype "passive"))
      (node (ref "U1") (pin "6") (pinfunction "UV_DELAY_6") (pintype "input"))
    )
    (net (code "30") (name "VDD") (class "Default")
      (node (ref "C15") (pin "2") (pinfunction "2_2") (pintype "passive"))
      (node (ref "D3") (pin "3") (pinfunction "A_3") (pintype "passive"))
      (node (ref "R10") (pin "2") (pinfunction "2_2") (pintype "passive"))
      (node (ref "U1") (pin "19") (pinfunction "VDD2_19") (pintype "power_in"))
      (node (ref "U1") (pin "24") (pinfunction "VDD1_24") (pintype "power_in"))
    )
    (net (code "31") (name "VLIN5") (class "Default")
      (node (ref "C18") (pin "2") (pinfunction "2_2") (pintype "passive"))
      (node (ref "R10") (pin "1") (pinfunction "1_1") (pintype "passive"))
      (node (ref "R9") (pin "1") (pinfunction "1_1") (pintype "passive"))
      (node (ref "U1") (pin "7") (pinfunction "VLIN5_7") (pintype "output"))
    )
    (net (code "32") (name "unconnected-(PF1-Pad1)") (class "Default")
      (node (ref "PF1") (pin "1") (pinfunction "1_1") (pintype "passive"))
    )
    (net (code "33") (name "unconnected-(PF1-Pad2)") (class "Default")
      (node (ref "PF1") (pin "2") (pinfunction "2_2") (pintype "passive"))
    )
  )
)
